# 30_PP0_PWR.net
KiCad netlist of a schematic drawn in Altium Designer
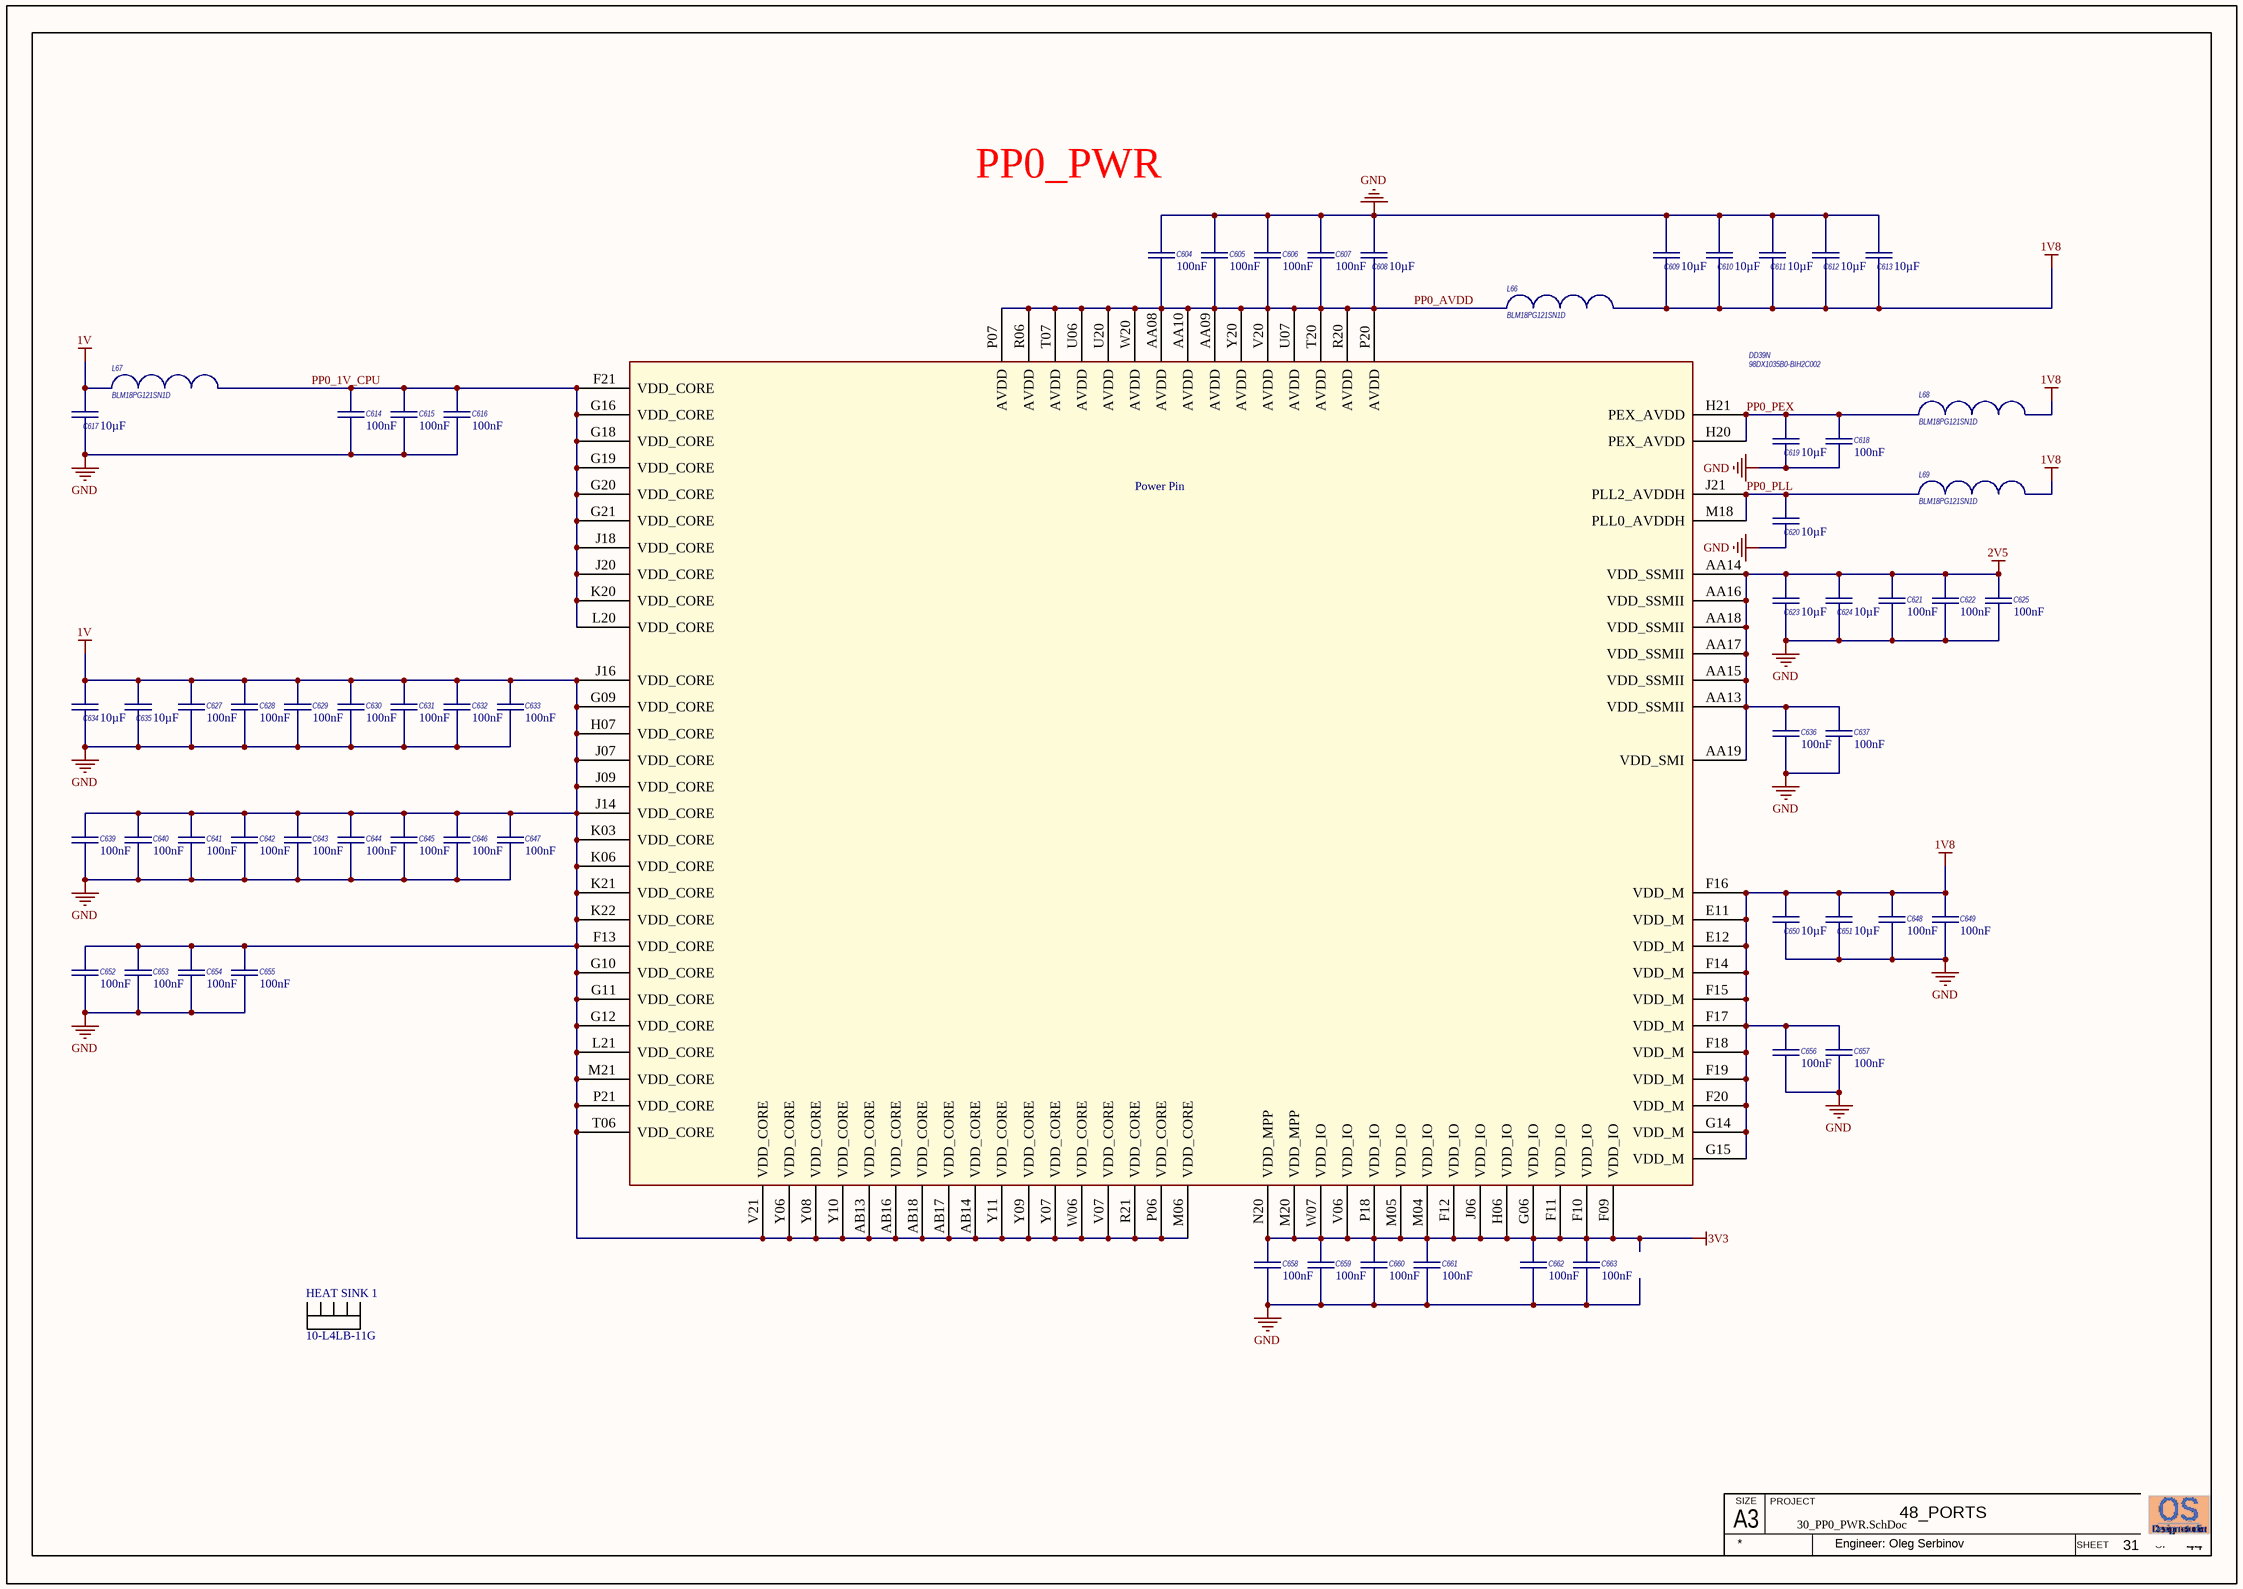
[diagram p0: 30_PP0_PWR.SchDoc]

(export (version "E")
  (design (tool "Eeschema 10.0.6"))
  (components
    (comp (ref "C604")
      (value "GRM155R71E104KE14D")
      (footprint "C0402_IPC High Density")
      (description "C0402, 100nF, 25V, X7R")
      (fields
        (field (name "MANUFACTURER") "Murata")
        (field (name "CAPACITANCE") "100nF")
        (field (name "CUSTOMER PART NUMBER") "Конденсатор, 100n, 0402, 25V, X7R, 10%")
      )
      (libsource (lib "CAPACITORS") (part "GRM155R71E104KE14D"))
    )
    (comp (ref "C605")
      (value "GRM155R71E104KE14D")
      (footprint "C0402_IPC High Density")
      (description "C0402, 100nF, 25V, X7R")
      (fields
        (field (name "MANUFACTURER") "Murata")
        (field (name "CAPACITANCE") "100nF")
        (field (name "CUSTOMER PART NUMBER") "Конденсатор, 100n, 0402, 25V, X7R, 10%")
      )
      (libsource (lib "CAPACITORS") (part "GRM155R71E104KE14D"))
    )
    (comp (ref "C606")
      (value "GRM155R71E104KE14D")
      (footprint "C0402_IPC High Density")
      (description "C0402, 100nF, 25V, X7R")
      (fields
        (field (name "MANUFACTURER") "Murata")
        (field (name "CAPACITANCE") "100nF")
        (field (name "CUSTOMER PART NUMBER") "Конденсатор, 100n, 0402, 25V, X7R, 10%")
      )
      (libsource (lib "CAPACITORS") (part "GRM155R71E104KE14D"))
    )
    (comp (ref "C607")
      (value "GRM155R71E104KE14D")
      (footprint "C0402_IPC High Density")
      (description "C0402, 100nF, 25V, X7R")
      (fields
        (field (name "MANUFACTURER") "Murata")
        (field (name "CAPACITANCE") "100nF")
        (field (name "CUSTOMER PART NUMBER") "Конденсатор, 100n, 0402, 25V, X7R, 10%")
      )
      (libsource (lib "CAPACITORS") (part "GRM155R71E104KE14D"))
    )
    (comp (ref "C608")
      (value "GRM21BR61C106KE15")
      (footprint "CAPC2012[0805]")
      (description "C0805, 10uF 10%, 16V, X5R")
      (fields
        (field (name "MANUFACTURER") "Murata")
        (field (name "TOLERANCE") "±10%")
        (field (name "CAPACITANCE") "10µF")
      )
      (libsource (lib "CAPACITORS") (part "GRM21BR61C106KE15"))
    )
    (comp (ref "C609")
      (value "GRM21BR61C106KE15")
      (footprint "CAPC2012[0805]")
      (description "C0805, 10uF 10%, 16V, X5R")
      (fields
        (field (name "MANUFACTURER") "Murata")
        (field (name "TOLERANCE") "±10%")
        (field (name "CAPACITANCE") "10µF")
      )
      (libsource (lib "CAPACITORS") (part "GRM21BR61C106KE15"))
    )
    (comp (ref "C610")
      (value "GRM21BR61C106KE15")
      (footprint "CAPC2012[0805]")
      (description "C0805, 10uF 10%, 16V, X5R")
      (fields
        (field (name "MANUFACTURER") "Murata")
        (field (name "TOLERANCE") "±10%")
        (field (name "CAPACITANCE") "10µF")
      )
      (libsource (lib "CAPACITORS") (part "GRM21BR61C106KE15"))
    )
    (comp (ref "C611")
      (value "GRM21BR61C106KE15")
      (footprint "CAPC2012[0805]")
      (description "C0805, 10uF 10%, 16V, X5R")
      (fields
        (field (name "MANUFACTURER") "Murata")
        (field (name "TOLERANCE") "±10%")
        (field (name "CAPACITANCE") "10µF")
      )
      (libsource (lib "CAPACITORS") (part "GRM21BR61C106KE15"))
    )
    (comp (ref "C612")
      (value "GRM21BR61C106KE15")
      (footprint "CAPC2012[0805]")
      (description "C0805, 10uF 10%, 16V, X5R")
      (fields
        (field (name "MANUFACTURER") "Murata")
        (field (name "TOLERANCE") "±10%")
        (field (name "CAPACITANCE") "10µF")
      )
      (libsource (lib "CAPACITORS") (part "GRM21BR61C106KE15"))
    )
    (comp (ref "C613")
      (value "GRM21BR61C106KE15")
      (footprint "CAPC2012[0805]")
      (description "C0805, 10uF 10%, 16V, X5R")
      (fields
        (field (name "MANUFACTURER") "Murata")
        (field (name "TOLERANCE") "±10%")
        (field (name "CAPACITANCE") "10µF")
      )
      (libsource (lib "CAPACITORS") (part "GRM21BR61C106KE15"))
    )
    (comp (ref "C614")
      (value "GRM155R71E104KE14D")
      (footprint "C0402_IPC High Density")
      (description "C0402, 100nF, 25V, X7R")
      (fields
        (field (name "MANUFACTURER") "Murata")
        (field (name "CAPACITANCE") "100nF")
        (field (name "CUSTOMER PART NUMBER") "Конденсатор, 100n, 0402, 25V, X7R, 10%")
      )
      (libsource (lib "CAPACITORS") (part "GRM155R71E104KE14D"))
    )
    (comp (ref "C615")
      (value "GRM155R71E104KE14D")
      (footprint "C0402_IPC High Density")
      (description "C0402, 100nF, 25V, X7R")
      (fields
        (field (name "MANUFACTURER") "Murata")
        (field (name "CAPACITANCE") "100nF")
        (field (name "CUSTOMER PART NUMBER") "Конденсатор, 100n, 0402, 25V, X7R, 10%")
      )
      (libsource (lib "CAPACITORS") (part "GRM155R71E104KE14D"))
    )
    (comp (ref "C616")
      (value "GRM155R71E104KE14D")
      (footprint "C0402_IPC High Density")
      (description "C0402, 100nF, 25V, X7R")
      (fields
        (field (name "MANUFACTURER") "Murata")
        (field (name "CAPACITANCE") "100nF")
        (field (name "CUSTOMER PART NUMBER") "Конденсатор, 100n, 0402, 25V, X7R, 10%")
      )
      (libsource (lib "CAPACITORS") (part "GRM155R71E104KE14D"))
    )
    (comp (ref "C617")
      (value "GRM21BR61C106KE15")
      (footprint "CAPC2012[0805]")
      (description "C0805, 10uF 10%, 16V, X5R")
      (fields
        (field (name "MANUFACTURER") "Murata")
        (field (name "TOLERANCE") "±10%")
        (field (name "CAPACITANCE") "10µF")
      )
      (libsource (lib "CAPACITORS") (part "GRM21BR61C106KE15"))
    )
    (comp (ref "C618")
      (value "GRM155R71E104KE14D")
      (footprint "C0402_IPC High Density")
      (description "C0402, 100nF, 25V, X7R")
      (fields
        (field (name "MANUFACTURER") "Murata")
        (field (name "CAPACITANCE") "100nF")
        (field (name "CUSTOMER PART NUMBER") "Конденсатор, 100n, 0402, 25V, X7R, 10%")
      )
      (libsource (lib "CAPACITORS") (part "GRM155R71E104KE14D"))
    )
    (comp (ref "C619")
      (value "GRM21BR61C106KE15")
      (footprint "CAPC2012[0805]")
      (description "C0805, 10uF 10%, 16V, X5R")
      (fields
        (field (name "MANUFACTURER") "Murata")
        (field (name "TOLERANCE") "±10%")
        (field (name "CAPACITANCE") "10µF")
      )
      (libsource (lib "CAPACITORS") (part "GRM21BR61C106KE15"))
    )
    (comp (ref "C620")
      (value "GRM21BR61C106KE15")
      (footprint "CAPC2012[0805]")
      (description "C0805, 10uF 10%, 16V, X5R")
      (fields
        (field (name "MANUFACTURER") "Murata")
        (field (name "TOLERANCE") "±10%")
        (field (name "CAPACITANCE") "10µF")
      )
      (libsource (lib "CAPACITORS") (part "GRM21BR61C106KE15"))
    )
    (comp (ref "C621")
      (value "GRM155R71E104KE14D")
      (footprint "C0402_IPC High Density")
      (description "C0402, 100nF, 25V, X7R")
      (fields
        (field (name "MANUFACTURER") "Murata")
        (field (name "CAPACITANCE") "100nF")
        (field (name "CUSTOMER PART NUMBER") "Конденсатор, 100n, 0402, 25V, X7R, 10%")
      )
      (libsource (lib "CAPACITORS") (part "GRM155R71E104KE14D"))
    )
    (comp (ref "C622")
      (value "GRM155R71E104KE14D")
      (footprint "C0402_IPC High Density")
      (description "C0402, 100nF, 25V, X7R")
      (fields
        (field (name "MANUFACTURER") "Murata")
        (field (name "CAPACITANCE") "100nF")
        (field (name "CUSTOMER PART NUMBER") "Конденсатор, 100n, 0402, 25V, X7R, 10%")
      )
      (libsource (lib "CAPACITORS") (part "GRM155R71E104KE14D"))
    )
    (comp (ref "C623")
      (value "GRM21BR61C106KE15")
      (footprint "CAPC2012[0805]")
      (description "C0805, 10uF 10%, 16V, X5R")
      (fields
        (field (name "MANUFACTURER") "Murata")
        (field (name "TOLERANCE") "±10%")
        (field (name "CAPACITANCE") "10µF")
      )
      (libsource (lib "CAPACITORS") (part "GRM21BR61C106KE15"))
    )
    (comp (ref "C624")
      (value "GRM21BR61C106KE15")
      (footprint "CAPC2012[0805]")
      (description "C0805, 10uF 10%, 16V, X5R")
      (fields
        (field (name "MANUFACTURER") "Murata")
        (field (name "TOLERANCE") "±10%")
        (field (name "CAPACITANCE") "10µF")
      )
      (libsource (lib "CAPACITORS") (part "GRM21BR61C106KE15"))
    )
    (comp (ref "C625")
      (value "GRM155R71E104KE14D")
      (footprint "C0402_IPC High Density")
      (description "C0402, 100nF, 25V, X7R")
      (fields
        (field (name "MANUFACTURER") "Murata")
        (field (name "CAPACITANCE") "100nF")
        (field (name "CUSTOMER PART NUMBER") "Конденсатор, 100n, 0402, 25V, X7R, 10%")
      )
      (libsource (lib "CAPACITORS") (part "GRM155R71E104KE14D"))
    )
    (comp (ref "C627")
      (value "GRM155R71E104KE14D")
      (footprint "C0402_IPC High Density")
      (description "C0402, 100nF, 25V, X7R")
      (fields
        (field (name "MANUFACTURER") "Murata")
        (field (name "CAPACITANCE") "100nF")
        (field (name "CUSTOMER PART NUMBER") "Конденсатор, 100n, 0402, 25V, X7R, 10%")
      )
      (libsource (lib "CAPACITORS") (part "GRM155R71E104KE14D"))
    )
    (comp (ref "C628")
      (value "GRM155R71E104KE14D")
      (footprint "C0402_IPC High Density")
      (description "C0402, 100nF, 25V, X7R")
      (fields
        (field (name "MANUFACTURER") "Murata")
        (field (name "CAPACITANCE") "100nF")
        (field (name "CUSTOMER PART NUMBER") "Конденсатор, 100n, 0402, 25V, X7R, 10%")
      )
      (libsource (lib "CAPACITORS") (part "GRM155R71E104KE14D"))
    )
    (comp (ref "C629")
      (value "GRM155R71E104KE14D")
      (footprint "C0402_IPC High Density")
      (description "C0402, 100nF, 25V, X7R")
      (fields
        (field (name "MANUFACTURER") "Murata")
        (field (name "CAPACITANCE") "100nF")
        (field (name "CUSTOMER PART NUMBER") "Конденсатор, 100n, 0402, 25V, X7R, 10%")
      )
      (libsource (lib "CAPACITORS") (part "GRM155R71E104KE14D"))
    )
    (comp (ref "C630")
      (value "GRM155R71E104KE14D")
      (footprint "C0402_IPC High Density")
      (description "C0402, 100nF, 25V, X7R")
      (fields
        (field (name "MANUFACTURER") "Murata")
        (field (name "CAPACITANCE") "100nF")
        (field (name "CUSTOMER PART NUMBER") "Конденсатор, 100n, 0402, 25V, X7R, 10%")
      )
      (libsource (lib "CAPACITORS") (part "GRM155R71E104KE14D"))
    )
    (comp (ref "C631")
      (value "GRM155R71E104KE14D")
      (footprint "C0402_IPC High Density")
      (description "C0402, 100nF, 25V, X7R")
      (fields
        (field (name "MANUFACTURER") "Murata")
        (field (name "CAPACITANCE") "100nF")
        (field (name "CUSTOMER PART NUMBER") "Конденсатор, 100n, 0402, 25V, X7R, 10%")
      )
      (libsource (lib "CAPACITORS") (part "GRM155R71E104KE14D"))
    )
    (comp (ref "C632")
      (value "GRM155R71E104KE14D")
      (footprint "C0402_IPC High Density")
      (description "C0402, 100nF, 25V, X7R")
      (fields
        (field (name "MANUFACTURER") "Murata")
        (field (name "CAPACITANCE") "100nF")
        (field (name "CUSTOMER PART NUMBER") "Конденсатор, 100n, 0402, 25V, X7R, 10%")
      )
      (libsource (lib "CAPACITORS") (part "GRM155R71E104KE14D"))
    )
    (comp (ref "C633")
      (value "GRM155R71E104KE14D")
      (footprint "C0402_IPC High Density")
      (description "C0402, 100nF, 25V, X7R")
      (fields
        (field (name "MANUFACTURER") "Murata")
        (field (name "CAPACITANCE") "100nF")
        (field (name "CUSTOMER PART NUMBER") "Конденсатор, 100n, 0402, 25V, X7R, 10%")
      )
      (libsource (lib "CAPACITORS") (part "GRM155R71E104KE14D"))
    )
    (comp (ref "C634")
      (value "GRM21BR61C106KE15")
      (footprint "CAPC2012[0805]")
      (description "C0805, 10uF 10%, 16V, X5R")
      (fields
        (field (name "MANUFACTURER") "Murata")
        (field (name "TOLERANCE") "±10%")
        (field (name "CAPACITANCE") "10µF")
      )
      (libsource (lib "CAPACITORS") (part "GRM21BR61C106KE15"))
    )
    (comp (ref "C635")
      (value "GRM21BR61C106KE15")
      (footprint "CAPC2012[0805]")
      (description "C0805, 10uF 10%, 16V, X5R")
      (fields
        (field (name "MANUFACTURER") "Murata")
        (field (name "TOLERANCE") "±10%")
        (field (name "CAPACITANCE") "10µF")
      )
      (libsource (lib "CAPACITORS") (part "GRM21BR61C106KE15"))
    )
    (comp (ref "C636")
      (value "GRM155R71E104KE14D")
      (footprint "C0402_IPC High Density")
      (description "C0402, 100nF, 25V, X7R")
      (fields
        (field (name "MANUFACTURER") "Murata")
        (field (name "CAPACITANCE") "100nF")
        (field (name "CUSTOMER PART NUMBER") "Конденсатор, 100n, 0402, 25V, X7R, 10%")
      )
      (libsource (lib "CAPACITORS") (part "GRM155R71E104KE14D"))
    )
    (comp (ref "C637")
      (value "GRM155R71E104KE14D")
      (footprint "C0402_IPC High Density")
      (description "C0402, 100nF, 25V, X7R")
      (fields
        (field (name "MANUFACTURER") "Murata")
        (field (name "CAPACITANCE") "100nF")
        (field (name "CUSTOMER PART NUMBER") "Конденсатор, 100n, 0402, 25V, X7R, 10%")
      )
      (libsource (lib "CAPACITORS") (part "GRM155R71E104KE14D"))
    )
    (comp (ref "C639")
      (value "GRM155R71E104KE14D")
      (footprint "C0402_IPC High Density")
      (description "C0402, 100nF, 25V, X7R")
      (fields
        (field (name "MANUFACTURER") "Murata")
        (field (name "CAPACITANCE") "100nF")
        (field (name "CUSTOMER PART NUMBER") "Конденсатор, 100n, 0402, 25V, X7R, 10%")
      )
      (libsource (lib "CAPACITORS") (part "GRM155R71E104KE14D"))
    )
    (comp (ref "C640")
      (value "GRM155R71E104KE14D")
      (footprint "C0402_IPC High Density")
      (description "C0402, 100nF, 25V, X7R")
      (fields
        (field (name "MANUFACTURER") "Murata")
        (field (name "CAPACITANCE") "100nF")
        (field (name "CUSTOMER PART NUMBER") "Конденсатор, 100n, 0402, 25V, X7R, 10%")
      )
      (libsource (lib "CAPACITORS") (part "GRM155R71E104KE14D"))
    )
    (comp (ref "C641")
      (value "GRM155R71E104KE14D")
      (footprint "C0402_IPC High Density")
      (description "C0402, 100nF, 25V, X7R")
      (fields
        (field (name "MANUFACTURER") "Murata")
        (field (name "CAPACITANCE") "100nF")
        (field (name "CUSTOMER PART NUMBER") "Конденсатор, 100n, 0402, 25V, X7R, 10%")
      )
      (libsource (lib "CAPACITORS") (part "GRM155R71E104KE14D"))
    )
    (comp (ref "C642")
      (value "GRM155R71E104KE14D")
      (footprint "C0402_IPC High Density")
      (description "C0402, 100nF, 25V, X7R")
      (fields
        (field (name "MANUFACTURER") "Murata")
        (field (name "CAPACITANCE") "100nF")
        (field (name "CUSTOMER PART NUMBER") "Конденсатор, 100n, 0402, 25V, X7R, 10%")
      )
      (libsource (lib "CAPACITORS") (part "GRM155R71E104KE14D"))
    )
    (comp (ref "C643")
      (value "GRM155R71E104KE14D")
      (footprint "C0402_IPC High Density")
      (description "C0402, 100nF, 25V, X7R")
      (fields
        (field (name "MANUFACTURER") "Murata")
        (field (name "CAPACITANCE") "100nF")
        (field (name "CUSTOMER PART NUMBER") "Конденсатор, 100n, 0402, 25V, X7R, 10%")
      )
      (libsource (lib "CAPACITORS") (part "GRM155R71E104KE14D"))
    )
    (comp (ref "C644")
      (value "GRM155R71E104KE14D")
      (footprint "C0402_IPC High Density")
      (description "C0402, 100nF, 25V, X7R")
      (fields
        (field (name "MANUFACTURER") "Murata")
        (field (name "CAPACITANCE") "100nF")
        (field (name "CUSTOMER PART NUMBER") "Конденсатор, 100n, 0402, 25V, X7R, 10%")
      )
      (libsource (lib "CAPACITORS") (part "GRM155R71E104KE14D"))
    )
    (comp (ref "C645")
      (value "GRM155R71E104KE14D")
      (footprint "C0402_IPC High Density")
      (description "C0402, 100nF, 25V, X7R")
      (fields
        (field (name "MANUFACTURER") "Murata")
        (field (name "CAPACITANCE") "100nF")
        (field (name "CUSTOMER PART NUMBER") "Конденсатор, 100n, 0402, 25V, X7R, 10%")
      )
      (libsource (lib "CAPACITORS") (part "GRM155R71E104KE14D"))
    )
    (comp (ref "C646")
      (value "GRM155R71E104KE14D")
      (footprint "C0402_IPC High Density")
      (description "C0402, 100nF, 25V, X7R")
      (fields
        (field (name "MANUFACTURER") "Murata")
        (field (name "CAPACITANCE") "100nF")
        (field (name "CUSTOMER PART NUMBER") "Конденсатор, 100n, 0402, 25V, X7R, 10%")
      )
      (libsource (lib "CAPACITORS") (part "GRM155R71E104KE14D"))
    )
    (comp (ref "C647")
      (value "GRM155R71E104KE14D")
      (footprint "C0402_IPC High Density")
      (description "C0402, 100nF, 25V, X7R")
      (fields
        (field (name "MANUFACTURER") "Murata")
        (field (name "CAPACITANCE") "100nF")
        (field (name "CUSTOMER PART NUMBER") "Конденсатор, 100n, 0402, 25V, X7R, 10%")
      )
      (libsource (lib "CAPACITORS") (part "GRM155R71E104KE14D"))
    )
    (comp (ref "C648")
      (value "GRM155R71E104KE14D")
      (footprint "C0402_IPC High Density")
      (description "C0402, 100nF, 25V, X7R")
      (fields
        (field (name "MANUFACTURER") "Murata")
        (field (name "CAPACITANCE") "100nF")
        (field (name "CUSTOMER PART NUMBER") "Конденсатор, 100n, 0402, 25V, X7R, 10%")
      )
      (libsource (lib "CAPACITORS") (part "GRM155R71E104KE14D"))
    )
    (comp (ref "C649")
      (value "GRM155R71E104KE14D")
      (footprint "C0402_IPC High Density")
      (description "C0402, 100nF, 25V, X7R")
      (fields
        (field (name "MANUFACTURER") "Murata")
        (field (name "CAPACITANCE") "100nF")
        (field (name "CUSTOMER PART NUMBER") "Конденсатор, 100n, 0402, 25V, X7R, 10%")
      )
      (libsource (lib "CAPACITORS") (part "GRM155R71E104KE14D"))
    )
    (comp (ref "C650")
      (value "GRM21BR61C106KE15")
      (footprint "CAPC2012[0805]")
      (description "C0805, 10uF 10%, 16V, X5R")
      (fields
        (field (name "MANUFACTURER") "Murata")
        (field (name "TOLERANCE") "±10%")
        (field (name "CAPACITANCE") "10µF")
      )
      (libsource (lib "CAPACITORS") (part "GRM21BR61C106KE15"))
    )
    (comp (ref "C651")
      (value "GRM21BR61C106KE15")
      (footprint "CAPC2012[0805]")
      (description "C0805, 10uF 10%, 16V, X5R")
      (fields
        (field (name "MANUFACTURER") "Murata")
        (field (name "TOLERANCE") "±10%")
        (field (name "CAPACITANCE") "10µF")
      )
      (libsource (lib "CAPACITORS") (part "GRM21BR61C106KE15"))
    )
    (comp (ref "C652")
      (value "GRM155R71E104KE14D")
      (footprint "C0402_IPC High Density")
      (description "C0402, 100nF, 25V, X7R")
      (fields
        (field (name "MANUFACTURER") "Murata")
        (field (name "CAPACITANCE") "100nF")
        (field (name "CUSTOMER PART NUMBER") "Конденсатор, 100n, 0402, 25V, X7R, 10%")
      )
      (libsource (lib "CAPACITORS") (part "GRM155R71E104KE14D"))
    )
    (comp (ref "C653")
      (value "GRM155R71E104KE14D")
      (footprint "C0402_IPC High Density")
      (description "C0402, 100nF, 25V, X7R")
      (fields
        (field (name "MANUFACTURER") "Murata")
        (field (name "CAPACITANCE") "100nF")
        (field (name "CUSTOMER PART NUMBER") "Конденсатор, 100n, 0402, 25V, X7R, 10%")
      )
      (libsource (lib "CAPACITORS") (part "GRM155R71E104KE14D"))
    )
    (comp (ref "C654")
      (value "GRM155R71E104KE14D")
      (footprint "C0402_IPC High Density")
      (description "C0402, 100nF, 25V, X7R")
      (fields
        (field (name "MANUFACTURER") "Murata")
        (field (name "CAPACITANCE") "100nF")
        (field (name "CUSTOMER PART NUMBER") "Конденсатор, 100n, 0402, 25V, X7R, 10%")
      )
      (libsource (lib "CAPACITORS") (part "GRM155R71E104KE14D"))
    )
    (comp (ref "C655")
      (value "GRM155R71E104KE14D")
      (footprint "C0402_IPC High Density")
      (description "C0402, 100nF, 25V, X7R")
      (fields
        (field (name "MANUFACTURER") "Murata")
        (field (name "CAPACITANCE") "100nF")
        (field (name "CUSTOMER PART NUMBER") "Конденсатор, 100n, 0402, 25V, X7R, 10%")
      )
      (libsource (lib "CAPACITORS") (part "GRM155R71E104KE14D"))
    )
    (comp (ref "C656")
      (value "GRM155R71E104KE14D")
      (footprint "C0402_IPC High Density")
      (description "C0402, 100nF, 25V, X7R")
      (fields
        (field (name "MANUFACTURER") "Murata")
        (field (name "CAPACITANCE") "100nF")
        (field (name "CUSTOMER PART NUMBER") "Конденсатор, 100n, 0402, 25V, X7R, 10%")
      )
      (libsource (lib "CAPACITORS") (part "GRM155R71E104KE14D"))
    )
    (comp (ref "C657")
      (value "GRM155R71E104KE14D")
      (footprint "C0402_IPC High Density")
      (description "C0402, 100nF, 25V, X7R")
      (fields
        (field (name "MANUFACTURER") "Murata")
        (field (name "CAPACITANCE") "100nF")
        (field (name "CUSTOMER PART NUMBER") "Конденсатор, 100n, 0402, 25V, X7R, 10%")
      )
      (libsource (lib "CAPACITORS") (part "GRM155R71E104KE14D"))
    )
    (comp (ref "C658")
      (value "GRM155R71E104KE14D")
      (footprint "C0402_IPC High Density")
      (description "C0402, 100nF, 25V, X7R")
      (fields
        (field (name "MANUFACTURER") "Murata")
        (field (name "CAPACITANCE") "100nF")
        (field (name "CUSTOMER PART NUMBER") "Конденсатор, 100n, 0402, 25V, X7R, 10%")
      )
      (libsource (lib "CAPACITORS") (part "GRM155R71E104KE14D"))
    )
    (comp (ref "C659")
      (value "GRM155R71E104KE14D")
      (footprint "C0402_IPC High Density")
      (description "C0402, 100nF, 25V, X7R")
      (fields
        (field (name "MANUFACTURER") "Murata")
        (field (name "CAPACITANCE") "100nF")
        (field (name "CUSTOMER PART NUMBER") "Конденсатор, 100n, 0402, 25V, X7R, 10%")
      )
      (libsource (lib "CAPACITORS") (part "GRM155R71E104KE14D"))
    )
    (comp (ref "C660")
      (value "GRM155R71E104KE14D")
      (footprint "C0402_IPC High Density")
      (description "C0402, 100nF, 25V, X7R")
      (fields
        (field (name "MANUFACTURER") "Murata")
        (field (name "CAPACITANCE") "100nF")
        (field (name "CUSTOMER PART NUMBER") "Конденсатор, 100n, 0402, 25V, X7R, 10%")
      )
      (libsource (lib "CAPACITORS") (part "GRM155R71E104KE14D"))
    )
    (comp (ref "C661")
      (value "GRM155R71E104KE14D")
      (footprint "C0402_IPC High Density")
      (description "C0402, 100nF, 25V, X7R")
      (fields
        (field (name "MANUFACTURER") "Murata")
        (field (name "CAPACITANCE") "100nF")
        (field (name "CUSTOMER PART NUMBER") "Конденсатор, 100n, 0402, 25V, X7R, 10%")
      )
      (libsource (lib "CAPACITORS") (part "GRM155R71E104KE14D"))
    )
    (comp (ref "C662")
      (value "GRM155R71E104KE14D")
      (footprint "C0402_IPC High Density")
      (description "C0402, 100nF, 25V, X7R")
      (fields
        (field (name "MANUFACTURER") "Murata")
        (field (name "CAPACITANCE") "100nF")
        (field (name "CUSTOMER PART NUMBER") "Конденсатор, 100n, 0402, 25V, X7R, 10%")
      )
      (libsource (lib "CAPACITORS") (part "GRM155R71E104KE14D"))
    )
    (comp (ref "C663")
      (value "GRM155R71E104KE14D")
      (footprint "C0402_IPC High Density")
      (description "C0402, 100nF, 25V, X7R")
      (fields
        (field (name "MANUFACTURER") "Murata")
        (field (name "CAPACITANCE") "100nF")
        (field (name "CUSTOMER PART NUMBER") "Конденсатор, 100n, 0402, 25V, X7R, 10%")
      )
      (libsource (lib "CAPACITORS") (part "GRM155R71E104KE14D"))
    )
    (comp (ref "DD39")
      (value "98DX1035B0-BIH2C002")
      (footprint "HSBGA617_27X27_1MM")
      (description "IC 24-PORT FE  4-PORT 2.5GE L2 ENTRY-LEVEL, CPU")
      (fields
        (field (name "CUSTOMER PART NUMBER") "Микросхема, 98DX1035B0-BIH2C002, IC 24-PORT FE 4-PORT 2.5GE L2 ENTRY-LEVEL, HSBGA617SBGA617")
        (field (name "MANUFACTURER") "Marvell Technology Group")
      )
      (libsource (lib "DIGITAL and ANALIG ICs") (part "98DX1035A1-BIH2C002"))
    )
    (comp (ref "HEAT SINK 1")
      (value "10-L4LB-11G")
      (footprint "10-L4LB-11G")
      (description "HEAT SINK  45.2x41.4")
      (fields
        (field (name "MANUFACTURER") "Aavid Thermalloy")
        (field (name "CUSTOMER PART NUMBER") "Радиатор, 10-L4LB-11G, Pin Fin heat sink with Push Pin attachment")
      )
      (libsource (lib "HEAT SINK") (part "10-L4LB-11G"))
    )
    (comp (ref "L66")
      (value "BLM18PG121SN1D")
      (footprint "INDC1608X95N")
      (description "FILTER BLM18 (0603, 2A)")
      (fields
        (field (name "MANUFACTURER") "Murata")
        (field (name "RPART NUMBER") "MPZ1608S121ATAH0 ; CIC10P121NC ; MPZ1608S121ATDH5 ; BLM18PG121SH1D ; 742792625")
      )
      (libsource (lib "INDUCTORS") (part "BLM18PG121SN1D"))
    )
    (comp (ref "L67")
      (value "BLM18PG121SN1D")
      (footprint "INDC1608X95N")
      (description "FILTER BLM18 (0603, 2A)")
      (fields
        (field (name "MANUFACTURER") "Murata")
        (field (name "RPART NUMBER") "MPZ1608S121ATAH0 ; CIC10P121NC ; MPZ1608S121ATDH5 ; BLM18PG121SH1D ; 742792625")
      )
      (libsource (lib "INDUCTORS") (part "BLM18PG121SN1D"))
    )
    (comp (ref "L68")
      (value "BLM18PG121SN1D")
      (footprint "INDC1608X95N")
      (description "FILTER BLM18 (0603, 2A)")
      (fields
        (field (name "MANUFACTURER") "Murata")
        (field (name "RPART NUMBER") "MPZ1608S121ATAH0 ; CIC10P121NC ; MPZ1608S121ATDH5 ; BLM18PG121SH1D ; 742792625")
      )
      (libsource (lib "INDUCTORS") (part "BLM18PG121SN1D"))
    )
    (comp (ref "L69")
      (value "BLM18PG121SN1D")
      (footprint "INDC1608X95N")
      (description "FILTER BLM18 (0603, 2A)")
      (fields
        (field (name "MANUFACTURER") "Murata")
        (field (name "RPART NUMBER") "MPZ1608S121ATAH0 ; CIC10P121NC ; MPZ1608S121ATDH5 ; BLM18PG121SH1D ; 742792625")
      )
      (libsource (lib "INDUCTORS") (part "BLM18PG121SN1D"))
    )
  )
  (nets
    (net (code "1") (name "/PP0_1V_CPU") (class "Default")
      (node (ref "C614") (pin "1") (pintype "passive"))
      (node (ref "C615") (pin "1") (pintype "passive"))
      (node (ref "C616") (pin "1") (pintype "passive"))
      (node (ref "DD39") (pin "F21") (pinfunction "VDD_CORE_F21") (pintype "power_in"))
      (node (ref "DD39") (pin "G16") (pinfunction "VDD_CORE_G16") (pintype "power_in"))
      (node (ref "DD39") (pin "G18") (pinfunction "VDD_CORE_G18") (pintype "power_in"))
      (node (ref "DD39") (pin "G19") (pinfunction "VDD_CORE_G19") (pintype "power_in"))
      (node (ref "DD39") (pin "G20") (pinfunction "VDD_CORE_G20") (pintype "power_in"))
      (node (ref "DD39") (pin "G21") (pinfunction "VDD_CORE_G21") (pintype "power_in"))
      (node (ref "DD39") (pin "J18") (pinfunction "VDD_CORE_J18") (pintype "power_in"))
      (node (ref "DD39") (pin "J20") (pinfunction "VDD_CORE_J20") (pintype "power_in"))
      (node (ref "DD39") (pin "K20") (pinfunction "VDD_CORE_K20") (pintype "power_in"))
      (node (ref "DD39") (pin "L20") (pinfunction "VDD_CORE_L20") (pintype "power_in"))
      (node (ref "L67") (pin "2") (pinfunction "2_2") (pintype "passive"))
    )
    (net (code "2") (name "/PP0_AVDD") (class "Default")
      (node (ref "C604") (pin "2") (pintype "passive"))
      (node (ref "C605") (pin "2") (pintype "passive"))
      (node (ref "C606") (pin "2") (pintype "passive"))
      (node (ref "C607") (pin "2") (pintype "passive"))
      (node (ref "C608") (pin "1") (pintype "passive"))
      (node (ref "DD39") (pin "AA08") (pinfunction "AVDD_AA08") (pintype "power_in"))
      (node (ref "DD39") (pin "AA09") (pinfunction "AVDD_AA09") (pintype "power_in"))
      (node (ref "DD39") (pin "AA10") (pinfunction "AVDD_AA10") (pintype "power_in"))
      (node (ref "DD39") (pin "P07") (pinfunction "AVDD_P07") (pintype "power_in"))
      (node (ref "DD39") (pin "P20") (pinfunction "AVDD_P20") (pintype "power_in"))
      (node (ref "DD39") (pin "R06") (pinfunction "AVDD_R06") (pintype "power_in"))
      (node (ref "DD39") (pin "R20") (pinfunction "AVDD_R20") (pintype "power_in"))
      (node (ref "DD39") (pin "T07") (pinfunction "AVDD_T07") (pintype "power_in"))
      (node (ref "DD39") (pin "T20") (pinfunction "AVDD_T20") (pintype "power_in"))
      (node (ref "DD39") (pin "U06") (pinfunction "AVDD_U06") (pintype "power_in"))
      (node (ref "DD39") (pin "U07") (pinfunction "AVDD_U07") (pintype "power_in"))
      (node (ref "DD39") (pin "U20") (pinfunction "AVDD_U20") (pintype "power_in"))
      (node (ref "DD39") (pin "V20") (pinfunction "AVDD_V20") (pintype "power_in"))
      (node (ref "DD39") (pin "W20") (pinfunction "AVDD_W20") (pintype "power_in"))
      (node (ref "DD39") (pin "Y20") (pinfunction "AVDD_Y20") (pintype "power_in"))
      (node (ref "L66") (pin "1") (pinfunction "1_1") (pintype "passive"))
    )
    (net (code "3") (name "/PP0_PEX") (class "Default")
      (node (ref "C618") (pin "1") (pintype "passive"))
      (node (ref "C619") (pin "2") (pintype "passive"))
      (node (ref "DD39") (pin "H20") (pinfunction "PEX_AVDD_H20") (pintype "power_in"))
      (node (ref "DD39") (pin "H21") (pinfunction "PEX_AVDD_H21") (pintype "power_in"))
      (node (ref "L68") (pin "1") (pinfunction "1_1") (pintype "passive"))
    )
    (net (code "4") (name "/PP0_PLL") (class "Default")
      (node (ref "C620") (pin "2") (pintype "passive"))
      (node (ref "DD39") (pin "J21") (pinfunction "PLL2_AVDDH_J21") (pintype "power_in"))
      (node (ref "DD39") (pin "M18") (pinfunction "PLL0_AVDDH_M18") (pintype "power_in"))
      (node (ref "L69") (pin "1") (pinfunction "1_1") (pintype "passive"))
    )
    (net (code "5") (name "1V") (class "Default")
      (node (ref "C617") (pin "2") (pintype "passive"))
      (node (ref "C627") (pin "1") (pintype "passive"))
      (node (ref "C628") (pin "1") (pintype "passive"))
      (node (ref "C629") (pin "1") (pintype "passive"))
      (node (ref "C630") (pin "1") (pintype "passive"))
      (node (ref "C631") (pin "1") (pintype "passive"))
      (node (ref "C632") (pin "1") (pintype "passive"))
      (node (ref "C633") (pin "1") (pintype "passive"))
      (node (ref "C634") (pin "2") (pintype "passive"))
      (node (ref "C635") (pin "2") (pintype "passive"))
      (node (ref "C639") (pin "1") (pintype "passive"))
      (node (ref "C640") (pin "1") (pintype "passive"))
      (node (ref "C641") (pin "1") (pintype "passive"))
      (node (ref "C642") (pin "1") (pintype "passive"))
      (node (ref "C643") (pin "1") (pintype "passive"))
      (node (ref "C644") (pin "1") (pintype "passive"))
      (node (ref "C645") (pin "1") (pintype "passive"))
      (node (ref "C646") (pin "1") (pintype "passive"))
      (node (ref "C647") (pin "1") (pintype "passive"))
      (node (ref "C652") (pin "1") (pintype "passive"))
      (node (ref "C653") (pin "1") (pintype "passive"))
      (node (ref "C654") (pin "1") (pintype "passive"))
      (node (ref "C655") (pin "1") (pintype "passive"))
      (node (ref "DD39") (pin "AB13") (pinfunction "VDD_CORE_AB13") (pintype "power_in"))
      (node (ref "DD39") (pin "AB14") (pinfunction "VDD_CORE_AB14") (pintype "power_in"))
      (node (ref "DD39") (pin "AB16") (pinfunction "VDD_CORE_AB16") (pintype "power_in"))
      (node (ref "DD39") (pin "AB17") (pinfunction "VDD_CORE_AB17") (pintype "power_in"))
      (node (ref "DD39") (pin "AB18") (pinfunction "VDD_CORE_AB18") (pintype "power_in"))
      (node (ref "DD39") (pin "F13") (pinfunction "VDD_CORE_F13") (pintype "power_in"))
      (node (ref "DD39") (pin "G09") (pinfunction "VDD_CORE_G09") (pintype "power_in"))
      (node (ref "DD39") (pin "G10") (pinfunction "VDD_CORE_G10") (pintype "power_in"))
      (node (ref "DD39") (pin "G11") (pinfunction "VDD_CORE_G11") (pintype "power_in"))
      (node (ref "DD39") (pin "G12") (pinfunction "VDD_CORE_G12") (pintype "power_in"))
      (node (ref "DD39") (pin "H07") (pinfunction "VDD_CORE_H07") (pintype "power_in"))
      (node (ref "DD39") (pin "J07") (pinfunction "VDD_CORE_J07") (pintype "power_in"))
      (node (ref "DD39") (pin "J09") (pinfunction "VDD_CORE_J09") (pintype "power_in"))
      (node (ref "DD39") (pin "J14") (pinfunction "VDD_CORE_J14") (pintype "power_in"))
      (node (ref "DD39") (pin "J16") (pinfunction "VDD_CORE_J16") (pintype "power_in"))
      (node (ref "DD39") (pin "K03") (pinfunction "VDD_CORE_K03") (pintype "power_in"))
      (node (ref "DD39") (pin "K06") (pinfunction "VDD_CORE_K06") (pintype "power_in"))
      (node (ref "DD39") (pin "K21") (pinfunction "VDD_CORE_K21") (pintype "power_in"))
      (node (ref "DD39") (pin "K22") (pinfunction "VDD_CORE_K22") (pintype "power_in"))
      (node (ref "DD39") (pin "L21") (pinfunction "VDD_CORE_L21") (pintype "power_in"))
      (node (ref "DD39") (pin "M06") (pinfunction "VDD_CORE_M06") (pintype "power_in"))
      (node (ref "DD39") (pin "M21") (pinfunction "VDD_CORE_M21") (pintype "power_in"))
      (node (ref "DD39") (pin "P06") (pinfunction "VDD_CORE_P06") (pintype "power_in"))
      (node (ref "DD39") (pin "P21") (pinfunction "VDD_CORE_P21") (pintype "power_in"))
      (node (ref "DD39") (pin "R21") (pinfunction "VDD_CORE_R21") (pintype "power_in"))
      (node (ref "DD39") (pin "T06") (pinfunction "VDD_CORE_T06") (pintype "power_in"))
      (node (ref "DD39") (pin "V07") (pinfunction "VDD_CORE_V07") (pintype "power_in"))
      (node (ref "DD39") (pin "V21") (pinfunction "VDD_CORE_V21") (pintype "power_in"))
      (node (ref "DD39") (pin "W06") (pinfunction "VDD_CORE_W06") (pintype "power_in"))
      (node (ref "DD39") (pin "Y06") (pinfunction "VDD_CORE_Y06") (pintype "power_in"))
      (node (ref "DD39") (pin "Y07") (pinfunction "VDD_CORE_Y07") (pintype "power_in"))
      (node (ref "DD39") (pin "Y08") (pinfunction "VDD_CORE_Y08") (pintype "power_in"))
      (node (ref "DD39") (pin "Y09") (pinfunction "VDD_CORE_Y09") (pintype "power_in"))
      (node (ref "DD39") (pin "Y10") (pinfunction "VDD_CORE_Y10") (pintype "power_in"))
      (node (ref "DD39") (pin "Y11") (pinfunction "VDD_CORE_Y11") (pintype "power_in"))
      (node (ref "L67") (pin "1") (pinfunction "1_1") (pintype "passive"))
    )
    (net (code "6") (name "1V8") (class "Default")
      (node (ref "C609") (pin "1") (pintype "passive"))
      (node (ref "C610") (pin "1") (pintype "passive"))
      (node (ref "C611") (pin "1") (pintype "passive"))
      (node (ref "C612") (pin "1") (pintype "passive"))
      (node (ref "C613") (pin "1") (pintype "passive"))
      (node (ref "C648") (pin "1") (pintype "passive"))
      (node (ref "C649") (pin "1") (pintype "passive"))
      (node (ref "C650") (pin "2") (pintype "passive"))
      (node (ref "C651") (pin "2") (pintype "passive"))
      (node (ref "C656") (pin "1") (pintype "passive"))
      (node (ref "C657") (pin "1") (pintype "passive"))
      (node (ref "DD39") (pin "E11") (pinfunction "VDD_M_E11") (pintype "power_in"))
      (node (ref "DD39") (pin "E12") (pinfunction "VDD_M_E12") (pintype "power_in"))
      (node (ref "DD39") (pin "F14") (pinfunction "VDD_M_F14") (pintype "power_in"))
      (node (ref "DD39") (pin "F15") (pinfunction "VDD_M_F15") (pintype "power_in"))
      (node (ref "DD39") (pin "F16") (pinfunction "VDD_M_F16") (pintype "power_in"))
      (node (ref "DD39") (pin "F17") (pinfunction "VDD_M_F17") (pintype "power_in"))
      (node (ref "DD39") (pin "F18") (pinfunction "VDD_M_F18") (pintype "power_in"))
      (node (ref "DD39") (pin "F19") (pinfunction "VDD_M_F19") (pintype "power_in"))
      (node (ref "DD39") (pin "F20") (pinfunction "VDD_M_F20") (pintype "power_in"))
      (node (ref "DD39") (pin "G14") (pinfunction "VDD_M_G14") (pintype "power_in"))
      (node (ref "DD39") (pin "G15") (pinfunction "VDD_M_G15") (pintype "power_in"))
      (node (ref "L66") (pin "2") (pinfunction "2_2") (pintype "passive"))
      (node (ref "L68") (pin "2") (pinfunction "2_2") (pintype "passive"))
      (node (ref "L69") (pin "2") (pinfunction "2_2") (pintype "passive"))
    )
    (net (code "7") (name "2V5") (class "Default")
      (node (ref "C621") (pin "1") (pintype "passive"))
      (node (ref "C622") (pin "1") (pintype "passive"))
      (node (ref "C623") (pin "2") (pintype "passive"))
      (node (ref "C624") (pin "2") (pintype "passive"))
      (node (ref "C625") (pin "1") (pintype "passive"))
      (node (ref "C636") (pin "1") (pintype "passive"))
      (node (ref "C637") (pin "1") (pintype "passive"))
      (node (ref "DD39") (pin "AA13") (pinfunction "VDD_SSMII_AA13") (pintype "power_in"))
      (node (ref "DD39") (pin "AA14") (pinfunction "VDD_SSMII_AA14") (pintype "power_in"))
      (node (ref "DD39") (pin "AA15") (pinfunction "VDD_SSMII_AA15") (pintype "power_in"))
      (node (ref "DD39") (pin "AA16") (pinfunction "VDD_SSMII_AA16") (pintype "power_in"))
      (node (ref "DD39") (pin "AA17") (pinfunction "VDD_SSMII_AA17") (pintype "power_in"))
      (node (ref "DD39") (pin "AA18") (pinfunction "VDD_SSMII_AA18") (pintype "power_in"))
      (node (ref "DD39") (pin "AA19") (pinfunction "VDD_SMI_AA19") (pintype "power_in"))
    )
    (net (code "8") (name "3V3") (class "Default")
      (node (ref "C658") (pin "1") (pintype "passive"))
      (node (ref "C659") (pin "1") (pintype "passive"))
      (node (ref "C660") (pin "1") (pintype "passive"))
      (node (ref "C661") (pin "1") (pintype "passive"))
      (node (ref "C662") (pin "1") (pintype "passive"))
      (node (ref "C663") (pin "1") (pintype "passive"))
      (node (ref "DD39") (pin "F09") (pinfunction "VDD_IO_F09") (pintype "power_in"))
      (node (ref "DD39") (pin "F10") (pinfunction "VDD_IO_F10") (pintype "power_in"))
      (node (ref "DD39") (pin "F11") (pinfunction "VDD_IO_F11") (pintype "power_in"))
      (node (ref "DD39") (pin "F12") (pinfunction "VDD_IO_F12") (pintype "power_in"))
      (node (ref "DD39") (pin "G06") (pinfunction "VDD_IO_G06") (pintype "power_in"))
      (node (ref "DD39") (pin "H06") (pinfunction "VDD_IO_H06") (pintype "power_in"))
      (node (ref "DD39") (pin "J06") (pinfunction "VDD_IO_J06") (pintype "power_in"))
      (node (ref "DD39") (pin "M04") (pinfunction "VDD_IO_M04") (pintype "power_in"))
      (node (ref "DD39") (pin "M05") (pinfunction "VDD_IO_M05") (pintype "power_in"))
      (node (ref "DD39") (pin "M20") (pinfunction "VDD_MPP_M20") (pintype "power_in"))
      (node (ref "DD39") (pin "N20") (pinfunction "VDD_MPP_N20") (pintype "power_in"))
      (node (ref "DD39") (pin "P18") (pinfunction "VDD_IO_P18") (pintype "power_in"))
      (node (ref "DD39") (pin "V06") (pinfunction "VDD_IO_V06") (pintype "power_in"))
      (node (ref "DD39") (pin "W07") (pinfunction "VDD_IO_W07") (pintype "power_in"))
    )
    (net (code "9") (name "GND") (class "Default")
      (node (ref "C604") (pin "1") (pintype "passive"))
      (node (ref "C605") (pin "1") (pintype "passive"))
      (node (ref "C606") (pin "1") (pintype "passive"))
      (node (ref "C607") (pin "1") (pintype "passive"))
      (node (ref "C608") (pin "2") (pintype "passive"))
      (node (ref "C609") (pin "2") (pintype "passive"))
      (node (ref "C610") (pin "2") (pintype "passive"))
      (node (ref "C611") (pin "2") (pintype "passive"))
      (node (ref "C612") (pin "2") (pintype "passive"))
      (node (ref "C613") (pin "2") (pintype "passive"))
      (node (ref "C614") (pin "2") (pintype "passive"))
      (node (ref "C615") (pin "2") (pintype "passive"))
      (node (ref "C616") (pin "2") (pintype "passive"))
      (node (ref "C617") (pin "1") (pintype "passive"))
      (node (ref "C618") (pin "2") (pintype "passive"))
      (node (ref "C619") (pin "1") (pintype "passive"))
      (node (ref "C620") (pin "1") (pintype "passive"))
      (node (ref "C621") (pin "2") (pintype "passive"))
      (node (ref "C622") (pin "2") (pintype "passive"))
      (node (ref "C623") (pin "1") (pintype "passive"))
      (node (ref "C624") (pin "1") (pintype "passive"))
      (node (ref "C625") (pin "2") (pintype "passive"))
      (node (ref "C627") (pin "2") (pintype "passive"))
      (node (ref "C628") (pin "2") (pintype "passive"))
      (node (ref "C629") (pin "2") (pintype "passive"))
      (node (ref "C630") (pin "2") (pintype "passive"))
      (node (ref "C631") (pin "2") (pintype "passive"))
      (node (ref "C632") (pin "2") (pintype "passive"))
      (node (ref "C633") (pin "2") (pintype "passive"))
      (node (ref "C634") (pin "1") (pintype "passive"))
      (node (ref "C635") (pin "1") (pintype "passive"))
      (node (ref "C636") (pin "2") (pintype "passive"))
      (node (ref "C637") (pin "2") (pintype "passive"))
      (node (ref "C639") (pin "2") (pintype "passive"))
      (node (ref "C640") (pin "2") (pintype "passive"))
      (node (ref "C641") (pin "2") (pintype "passive"))
      (node (ref "C642") (pin "2") (pintype "passive"))
      (node (ref "C643") (pin "2") (pintype "passive"))
      (node (ref "C644") (pin "2") (pintype "passive"))
      (node (ref "C645") (pin "2") (pintype "passive"))
      (node (ref "C646") (pin "2") (pintype "passive"))
      (node (ref "C647") (pin "2") (pintype "passive"))
      (node (ref "C648") (pin "2") (pintype "passive"))
      (node (ref "C649") (pin "2") (pintype "passive"))
      (node (ref "C650") (pin "1") (pintype "passive"))
      (node (ref "C651") (pin "1") (pintype "passive"))
      (node (ref "C652") (pin "2") (pintype "passive"))
      (node (ref "C653") (pin "2") (pintype "passive"))
      (node (ref "C654") (pin "2") (pintype "passive"))
      (node (ref "C655") (pin "2") (pintype "passive"))
      (node (ref "C656") (pin "2") (pintype "passive"))
      (node (ref "C657") (pin "2") (pintype "passive"))
      (node (ref "C658") (pin "2") (pintype "passive"))
      (node (ref "C659") (pin "2") (pintype "passive"))
      (node (ref "C660") (pin "2") (pintype "passive"))
      (node (ref "C661") (pin "2") (pintype "passive"))
      (node (ref "C662") (pin "2") (pintype "passive"))
      (node (ref "C663") (pin "2") (pintype "passive"))
    )
  )
)
